# EnviroTron.net
KiCad netlist of a schematic drawn in EAGLE
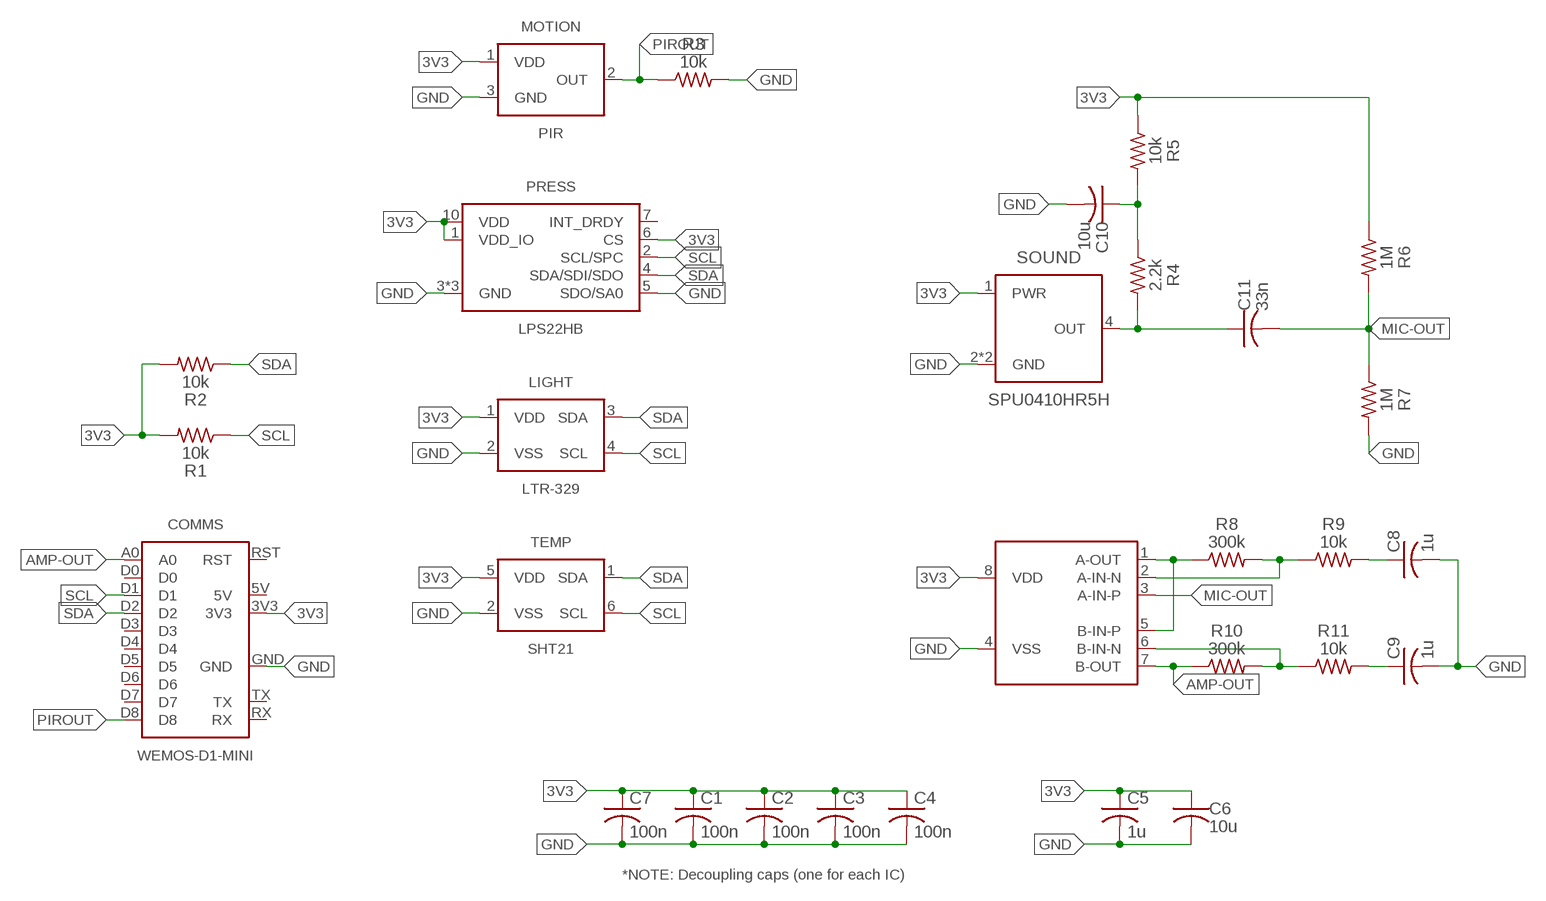
[diagram p0: schematic, sheet 1]

(export (version "E")
  (design (tool "Eeschema 10.0.6"))
  (components
    (comp (ref "C1")
      (value "100n")
      (footprint "eagle-import:C0603")
      (libsource (lib "eagle-import") (part "C-USC0603"))
    )
    (comp (ref "C2")
      (value "100n")
      (footprint "eagle-import:C0603")
      (libsource (lib "eagle-import") (part "C-USC0603"))
    )
    (comp (ref "C3")
      (value "100n")
      (footprint "eagle-import:C0603")
      (libsource (lib "eagle-import") (part "C-USC0603"))
    )
    (comp (ref "C4")
      (value "100n")
      (footprint "eagle-import:C0603")
      (libsource (lib "eagle-import") (part "C-USC0603"))
    )
    (comp (ref "C5")
      (value "1u")
      (footprint "eagle-import:C0603")
      (libsource (lib "eagle-import") (part "C-USC0603"))
    )
    (comp (ref "C6")
      (value "10u")
      (footprint "eagle-import:C0805")
      (libsource (lib "eagle-import") (part "rcl_C-USC0805"))
    )
    (comp (ref "C7")
      (value "100n")
      (footprint "eagle-import:C0603")
      (libsource (lib "eagle-import") (part "C-USC0603"))
    )
    (comp (ref "C8")
      (value "1u")
      (footprint "eagle-import:C0603")
      (libsource (lib "eagle-import") (part "C-USC0603"))
    )
    (comp (ref "C9")
      (value "1u")
      (footprint "eagle-import:C0603")
      (libsource (lib "eagle-import") (part "C-USC0603"))
    )
    (comp (ref "C10")
      (value "10u")
      (footprint "eagle-import:C0805")
      (libsource (lib "eagle-import") (part "rcl_C-USC0805"))
    )
    (comp (ref "C11")
      (value "33n")
      (footprint "eagle-import:C0805")
      (libsource (lib "eagle-import") (part "rcl_C-USC0805"))
    )
    (comp (ref "COMMS")
      (value "WEMOS-D1-MINI")
      (footprint "eagle-import:WEMOS-D1-MINI")
      (libsource (lib "eagle-import") (part "WEMOS-D1-MINI"))
    )
    (comp (ref "LIGHT")
      (value "LTR-329")
      (footprint "eagle-import:CHIPLED4")
      (libsource (lib "eagle-import") (part "LTR-329"))
    )
    (comp (ref "MOTION")
      (value "PIR")
      (footprint "eagle-import:CAN3")
      (libsource (lib "eagle-import") (part "PIR"))
    )
    (comp (ref "PRESS")
      (value "LPS22HB")
      (footprint "eagle-import:HLGA-10L")
      (fields (field (name "MANUFACTURER") "STMicroelectronics") (field (name "MPN") "LPS22HBTR"))
      (libsource (lib "eagle-import") (part "LPS22HB"))
    )
    (comp (ref "R1")
      (value "10k")
      (footprint "eagle-import:R0603")
      (libsource (lib "eagle-import") (part "R-US_R0603"))
    )
    (comp (ref "R2")
      (value "10k")
      (footprint "eagle-import:R0603")
      (libsource (lib "eagle-import") (part "R-US_R0603"))
    )
    (comp (ref "R3")
      (value "10k")
      (footprint "eagle-import:R0603")
      (libsource (lib "eagle-import") (part "R-US_R0603"))
    )
    (comp (ref "R4")
      (value "2.2k")
      (footprint "eagle-import:R0603")
      (libsource (lib "eagle-import") (part "R-US_R0603"))
    )
    (comp (ref "R5")
      (value "10k")
      (footprint "eagle-import:R0603")
      (libsource (lib "eagle-import") (part "R-US_R0603"))
    )
    (comp (ref "R6")
      (value "1M")
      (footprint "eagle-import:R0603")
      (libsource (lib "eagle-import") (part "R-US_R0603"))
    )
    (comp (ref "R7")
      (value "1M")
      (footprint "eagle-import:R0603")
      (libsource (lib "eagle-import") (part "R-US_R0603"))
    )
    (comp (ref "R8")
      (value "300k")
      (footprint "eagle-import:R0603")
      (libsource (lib "eagle-import") (part "R-US_R0603"))
    )
    (comp (ref "R9")
      (value "10k")
      (footprint "eagle-import:R0603")
      (libsource (lib "eagle-import") (part "R-US_R0603"))
    )
    (comp (ref "R10")
      (value "300k")
      (footprint "eagle-import:R0603")
      (libsource (lib "eagle-import") (part "R-US_R0603"))
    )
    (comp (ref "R11")
      (value "10k")
      (footprint "eagle-import:R0603")
      (libsource (lib "eagle-import") (part "R-US_R0603"))
    )
    (comp (ref "SOUND")
      (value "SPU0410HR5H")
      (footprint "eagle-import:BPAD-4")
      (fields (field (name "MPN") "SPU0410HR5H-PB"))
      (libsource (lib "eagle-import") (part "SPU0410HR5H"))
    )
    (comp (ref "TEMP")
      (value "SHT21")
      (footprint "eagle-import:SHT2X-DFN6")
      (libsource (lib "eagle-import") (part "SHT21"))
    )
    (comp (ref "U$1")
      (value "MCP6002")
      (footprint "eagle-import:MSOP-8")
      (fields (field (name "MPN") "MCP6002T-I/MS"))
      (libsource (lib "eagle-import") (part "MCP6002"))
    )
  )
  (nets
    (net (code "1") (name "3V3") (class "Default")
      (node (ref "C1") (pin "1") (pinfunction "1_1") (pintype "passive"))
      (node (ref "C2") (pin "1") (pinfunction "1_1") (pintype "passive"))
      (node (ref "C3") (pin "1") (pinfunction "1_1") (pintype "passive"))
      (node (ref "C4") (pin "1") (pinfunction "1_1") (pintype "passive"))
      (node (ref "C5") (pin "1") (pinfunction "1_1") (pintype "passive"))
      (node (ref "C6") (pin "1") (pinfunction "1_1") (pintype "passive"))
      (node (ref "C7") (pin "1") (pinfunction "1_1") (pintype "passive"))
      (node (ref "COMMS") (pin "3V3") (pinfunction "3V3_3V3") (pintype "bidirectional"))
      (node (ref "LIGHT") (pin "1") (pinfunction "VDD_1") (pintype "bidirectional"))
      (node (ref "MOTION") (pin "1") (pinfunction "VDD_1") (pintype "bidirectional"))
      (node (ref "PRESS") (pin "1") (pinfunction "VDD_IO_1") (pintype "bidirectional"))
      (node (ref "PRESS") (pin "10") (pinfunction "VDD_10") (pintype "bidirectional"))
      (node (ref "PRESS") (pin "6") (pinfunction "CS_6") (pintype "bidirectional"))
      (node (ref "R1") (pin "2") (pinfunction "2_2") (pintype "passive"))
      (node (ref "R2") (pin "2") (pinfunction "2_2") (pintype "passive"))
      (node (ref "R5") (pin "1") (pinfunction "1_1") (pintype "passive"))
      (node (ref "R6") (pin "1") (pinfunction "1_1") (pintype "passive"))
      (node (ref "SOUND") (pin "1") (pinfunction "PWR_1") (pintype "bidirectional"))
      (node (ref "TEMP") (pin "5") (pinfunction "VDD_5") (pintype "bidirectional"))
      (node (ref "U$1") (pin "8") (pinfunction "VDD_8") (pintype "bidirectional"))
    )
    (net (code "2") (name "AMP-OUT") (class "Default")
      (node (ref "COMMS") (pin "A0") (pinfunction "A0_A0") (pintype "bidirectional"))
      (node (ref "R10") (pin "1") (pinfunction "1_1") (pintype "passive"))
      (node (ref "U$1") (pin "7") (pinfunction "B-OUT_7") (pintype "bidirectional"))
    )
    (net (code "3") (name "GND") (class "Default")
      (node (ref "C1") (pin "2") (pinfunction "2_2") (pintype "passive"))
      (node (ref "C10") (pin "2") (pinfunction "2_2") (pintype "passive"))
      (node (ref "C2") (pin "2") (pinfunction "2_2") (pintype "passive"))
      (node (ref "C3") (pin "2") (pinfunction "2_2") (pintype "passive"))
      (node (ref "C4") (pin "2") (pinfunction "2_2") (pintype "passive"))
      (node (ref "C5") (pin "2") (pinfunction "2_2") (pintype "passive"))
      (node (ref "C6") (pin "2") (pinfunction "2_2") (pintype "passive"))
      (node (ref "C7") (pin "2") (pinfunction "2_2") (pintype "passive"))
      (node (ref "C8") (pin "2") (pinfunction "2_2") (pintype "passive"))
      (node (ref "C9") (pin "2") (pinfunction "2_2") (pintype "passive"))
      (node (ref "COMMS") (pin "GND") (pinfunction "GND_GND") (pintype "bidirectional"))
      (node (ref "LIGHT") (pin "2") (pinfunction "VSS_2") (pintype "bidirectional"))
      (node (ref "MOTION") (pin "3") (pinfunction "GND_3") (pintype "bidirectional"))
      (node (ref "PRESS") (pin "3") (pinfunction "GND_3") (pintype "bidirectional"))
      (node (ref "PRESS") (pin "5") (pinfunction "SDO/SA0_5") (pintype "bidirectional"))
      (node (ref "PRESS") (pin "8") (pinfunction "GND_8") (pintype "bidirectional"))
      (node (ref "PRESS") (pin "9") (pinfunction "GND_9") (pintype "bidirectional"))
      (node (ref "R3") (pin "2") (pinfunction "2_2") (pintype "passive"))
      (node (ref "R7") (pin "2") (pinfunction "2_2") (pintype "passive"))
      (node (ref "SOUND") (pin "2") (pinfunction "GND_2") (pintype "bidirectional"))
      (node (ref "SOUND") (pin "3") (pinfunction "GND_3") (pintype "bidirectional"))
      (node (ref "TEMP") (pin "2") (pinfunction "VSS_2") (pintype "bidirectional"))
      (node (ref "U$1") (pin "4") (pinfunction "VSS_4") (pintype "bidirectional"))
    )
    (net (code "4") (name "MIC-OUT") (class "Default")
      (node (ref "C11") (pin "2") (pinfunction "2_2") (pintype "passive"))
      (node (ref "R6") (pin "2") (pinfunction "2_2") (pintype "passive"))
      (node (ref "R7") (pin "1") (pinfunction "1_1") (pintype "passive"))
      (node (ref "U$1") (pin "3") (pinfunction "A-IN-P_3") (pintype "bidirectional"))
    )
    (net (code "5") (name "Net-(C8-Pad1)") (class "Default")
      (node (ref "C8") (pin "1") (pinfunction "1_1") (pintype "passive"))
      (node (ref "R9") (pin "2") (pinfunction "2_2") (pintype "passive"))
    )
    (net (code "6") (name "Net-(C9-Pad1)") (class "Default")
      (node (ref "C9") (pin "1") (pinfunction "1_1") (pintype "passive"))
      (node (ref "R11") (pin "2") (pinfunction "2_2") (pintype "passive"))
    )
    (net (code "7") (name "Net-(C10-Pad1)") (class "Default")
      (node (ref "C10") (pin "1") (pinfunction "1_1") (pintype "passive"))
      (node (ref "R4") (pin "1") (pinfunction "1_1") (pintype "passive"))
      (node (ref "R5") (pin "2") (pinfunction "2_2") (pintype "passive"))
    )
    (net (code "8") (name "Net-(SOUND-OUT)") (class "Default")
      (node (ref "C11") (pin "1") (pinfunction "1_1") (pintype "passive"))
      (node (ref "R4") (pin "2") (pinfunction "2_2") (pintype "passive"))
      (node (ref "SOUND") (pin "4") (pinfunction "OUT_4") (pintype "bidirectional"))
    )
    (net (code "9") (name "Net-(U$1-A-IN-N)") (class "Default")
      (node (ref "R8") (pin "2") (pinfunction "2_2") (pintype "passive"))
      (node (ref "R9") (pin "1") (pinfunction "1_1") (pintype "passive"))
      (node (ref "U$1") (pin "2") (pinfunction "A-IN-N_2") (pintype "bidirectional"))
    )
    (net (code "10") (name "Net-(U$1-A-OUT)") (class "Default")
      (node (ref "R8") (pin "1") (pinfunction "1_1") (pintype "passive"))
      (node (ref "U$1") (pin "1") (pinfunction "A-OUT_1") (pintype "bidirectional"))
      (node (ref "U$1") (pin "5") (pinfunction "B-IN-P_5") (pintype "bidirectional"))
    )
    (net (code "11") (name "Net-(U$1-B-IN-N)") (class "Default")
      (node (ref "R10") (pin "2") (pinfunction "2_2") (pintype "passive"))
      (node (ref "R11") (pin "1") (pinfunction "1_1") (pintype "passive"))
      (node (ref "U$1") (pin "6") (pinfunction "B-IN-N_6") (pintype "bidirectional"))
    )
    (net (code "12") (name "PIROUT") (class "Default")
      (node (ref "COMMS") (pin "D8") (pinfunction "D8_D8") (pintype "bidirectional"))
      (node (ref "MOTION") (pin "2") (pinfunction "OUT_2") (pintype "bidirectional"))
      (node (ref "R3") (pin "1") (pinfunction "1_1") (pintype "passive"))
    )
    (net (code "13") (name "SCL") (class "Default")
      (node (ref "COMMS") (pin "D1") (pinfunction "D1_D1") (pintype "bidirectional"))
      (node (ref "LIGHT") (pin "4") (pinfunction "SCL_4") (pintype "bidirectional"))
      (node (ref "PRESS") (pin "2") (pinfunction "SCL/SPC_2") (pintype "bidirectional"))
      (node (ref "R1") (pin "1") (pinfunction "1_1") (pintype "passive"))
      (node (ref "TEMP") (pin "6") (pinfunction "SCL_6") (pintype "bidirectional"))
    )
    (net (code "14") (name "SDA") (class "Default")
      (node (ref "COMMS") (pin "D2") (pinfunction "D2_D2") (pintype "bidirectional"))
      (node (ref "LIGHT") (pin "3") (pinfunction "SDA_3") (pintype "bidirectional"))
      (node (ref "PRESS") (pin "4") (pinfunction "SDA/SDI/SDO_4") (pintype "bidirectional"))
      (node (ref "R2") (pin "1") (pinfunction "1_1") (pintype "passive"))
      (node (ref "TEMP") (pin "1") (pinfunction "SDA_1") (pintype "bidirectional"))
    )
    (net (code "15") (name "unconnected-(COMMS-Pad5V)") (class "Default")
      (node (ref "COMMS") (pin "5V") (pinfunction "5V_5V") (pintype "bidirectional"))
    )
    (net (code "16") (name "unconnected-(COMMS-PadD0)") (class "Default")
      (node (ref "COMMS") (pin "D0") (pinfunction "D0_D0") (pintype "bidirectional"))
    )
    (net (code "17") (name "unconnected-(COMMS-PadD3)") (class "Default")
      (node (ref "COMMS") (pin "D3") (pinfunction "D3_D3") (pintype "bidirectional"))
    )
    (net (code "18") (name "unconnected-(COMMS-PadD4)") (class "Default")
      (node (ref "COMMS") (pin "D4") (pinfunction "D4_D4") (pintype "bidirectional"))
    )
    (net (code "19") (name "unconnected-(COMMS-PadD5)") (class "Default")
      (node (ref "COMMS") (pin "D5") (pinfunction "D5_D5") (pintype "bidirectional"))
    )
    (net (code "20") (name "unconnected-(COMMS-PadD6)") (class "Default")
      (node (ref "COMMS") (pin "D6") (pinfunction "D6_D6") (pintype "bidirectional"))
    )
    (net (code "21") (name "unconnected-(COMMS-PadD7)") (class "Default")
      (node (ref "COMMS") (pin "D7") (pinfunction "D7_D7") (pintype "bidirectional"))
    )
    (net (code "22") (name "unconnected-(COMMS-PadRST)") (class "Default")
      (node (ref "COMMS") (pin "RST") (pinfunction "RST_RST") (pintype "bidirectional"))
    )
    (net (code "23") (name "unconnected-(COMMS-PadRX)") (class "Default")
      (node (ref "COMMS") (pin "RX") (pinfunction "RX_RX") (pintype "bidirectional"))
    )
    (net (code "24") (name "unconnected-(COMMS-PadTX)") (class "Default")
      (node (ref "COMMS") (pin "TX") (pinfunction "TX_TX") (pintype "bidirectional"))
    )
    (net (code "25") (name "unconnected-(PRESS-INT_DRDY-Pad7)") (class "Default")
      (node (ref "PRESS") (pin "7") (pinfunction "INT_DRDY_7") (pintype "bidirectional"))
    )
  )
)
